# p128b.net
KiCad netlist of a schematic drawn in EAGLE
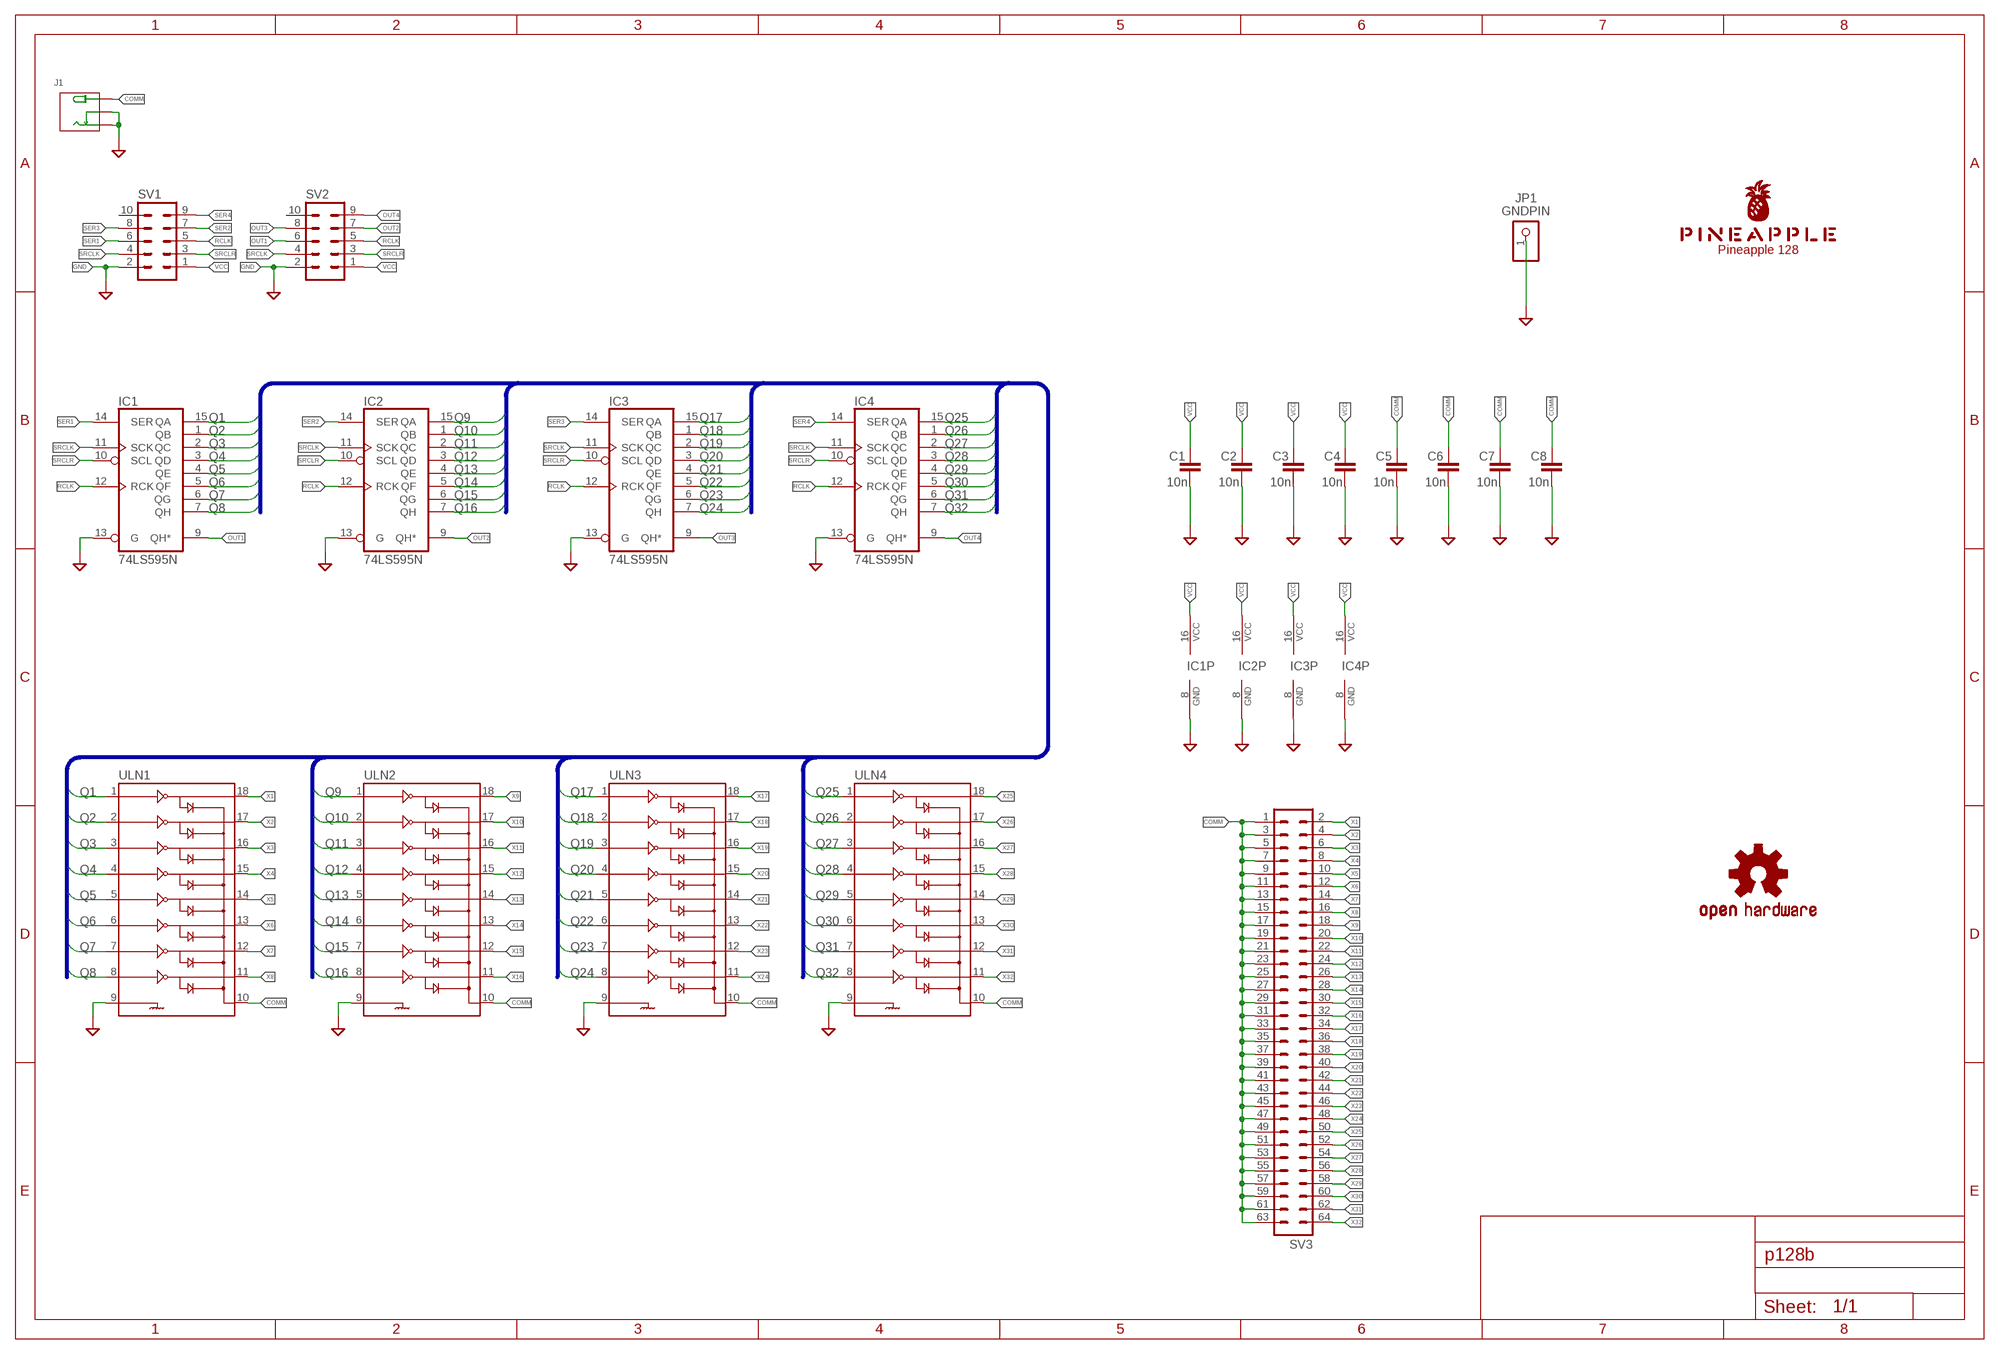
[diagram p0: schematic, sheet 1]

(export (version "E")
  (design (tool "Eeschema 10.0.6"))
  (components
    (comp (ref "C1")
      (value "10n")
      (footprint "eagle-import:C025-024X044")
      (libsource (lib "eagle-import") (part "resistor_348_C-EU025-024X044"))
    )
    (comp (ref "C2")
      (value "10n")
      (footprint "eagle-import:C025-024X044")
      (libsource (lib "eagle-import") (part "resistor_348_C-EU025-024X044"))
    )
    (comp (ref "C3")
      (value "10n")
      (footprint "eagle-import:C025-024X044")
      (libsource (lib "eagle-import") (part "resistor_348_C-EU025-024X044"))
    )
    (comp (ref "C4")
      (value "10n")
      (footprint "eagle-import:C025-024X044")
      (libsource (lib "eagle-import") (part "resistor_348_C-EU025-024X044"))
    )
    (comp (ref "C5")
      (value "10n")
      (footprint "eagle-import:C025-024X044")
      (libsource (lib "eagle-import") (part "C-EU025-024X044"))
    )
    (comp (ref "C6")
      (value "10n")
      (footprint "eagle-import:C025-024X044")
      (libsource (lib "eagle-import") (part "resistor_348_C-EU025-024X044"))
    )
    (comp (ref "C7")
      (value "10n")
      (footprint "eagle-import:C025-024X044")
      (libsource (lib "eagle-import") (part "resistor_348_C-EU025-024X044"))
    )
    (comp (ref "C8")
      (value "10n")
      (footprint "eagle-import:C025-024X044")
      (libsource (lib "eagle-import") (part "resistor_348_C-EU025-024X044"))
    )
    (comp (ref "IC1")
      (value "74LS595N")
      (footprint "eagle-import:DIL16")
      (libsource (lib "eagle-import") (part "74595NLS"))
    )
    (comp (ref "IC2")
      (value "74LS595N")
      (footprint "eagle-import:DIL16")
      (libsource (lib "eagle-import") (part "74595NLS"))
    )
    (comp (ref "IC3")
      (value "74LS595N")
      (footprint "eagle-import:DIL16")
      (libsource (lib "eagle-import") (part "74595NLS"))
    )
    (comp (ref "IC4")
      (value "74LS595N")
      (footprint "eagle-import:DIL16")
      (libsource (lib "eagle-import") (part "74595NLS"))
    )
    (comp (ref "J1")
      (value "JACK-DC-005'DC-005'")
      (footprint "eagle-import:3P-L14.2_W11.0_H9.0MM")
      (libsource (lib "eagle-import") (part "JACK-DC-005'DC-005'"))
    )
    (comp (ref "JP1")
      (value "GNDPIN")
      (footprint "eagle-import:1X01")
      (libsource (lib "eagle-import") (part "PINHD-1X1"))
    )
    (comp (ref "LOGO1")
      (value "OSHW-LOGOS-COPPER")
      (footprint "eagle-import:OSHW-LOGO-S_COPPER")
      (libsource (lib "eagle-import") (part "OSHW-LOGOS-COPPER"))
    )
    (comp (ref "SV1")
      (value "ML10L")
      (footprint "eagle-import:ML10L")
      (libsource (lib "eagle-import") (part "ML10L"))
    )
    (comp (ref "SV2")
      (value "ML10L")
      (footprint "eagle-import:ML10L")
      (libsource (lib "eagle-import") (part "ML10L"))
    )
    (comp (ref "SV3")
      (value "ML64L")
      (footprint "eagle-import:ML64L")
      (libsource (lib "eagle-import") (part "ML64L"))
    )
    (comp (ref "U$1")
      (value "PINEAPPLE450_SILK")
      (footprint "eagle-import:PINEAPPLE450_SILK")
      (libsource (lib "eagle-import") (part "PINEAPPLE450_SILK"))
    )
    (comp (ref "ULN1")
      (value "ULN2803DIP")
      (footprint "eagle-import:DIL18")
      (libsource (lib "eagle-import") (part "ULN2803DIP"))
    )
    (comp (ref "ULN2")
      (value "ULN2803DIP")
      (footprint "eagle-import:DIL18")
      (libsource (lib "eagle-import") (part "ULN2803DIP"))
    )
    (comp (ref "ULN3")
      (value "ULN2803DIP")
      (footprint "eagle-import:DIL18")
      (libsource (lib "eagle-import") (part "ULN2803DIP"))
    )
    (comp (ref "ULN4")
      (value "ULN2803DIP")
      (footprint "eagle-import:DIL18")
      (libsource (lib "eagle-import") (part "ULN2803DIP"))
    )
  )
  (nets
    (net (code "1") (name "/Q1") (class "Default")
      (node (ref "IC1") (pin "15") (pinfunction "QA_15") (pintype "tri_state"))
      (node (ref "ULN1") (pin "1") (pinfunction "1_1") (pintype "bidirectional"))
    )
    (net (code "2") (name "/Q2") (class "Default")
      (node (ref "IC1") (pin "1") (pinfunction "QB_1") (pintype "tri_state"))
      (node (ref "ULN1") (pin "2") (pinfunction "2_2") (pintype "bidirectional"))
    )
    (net (code "3") (name "/Q3") (class "Default")
      (node (ref "IC1") (pin "2") (pinfunction "QC_2") (pintype "tri_state"))
      (node (ref "ULN1") (pin "3") (pinfunction "3_3") (pintype "bidirectional"))
    )
    (net (code "4") (name "/Q4") (class "Default")
      (node (ref "IC1") (pin "3") (pinfunction "QD_3") (pintype "tri_state"))
      (node (ref "ULN1") (pin "4") (pinfunction "4_4") (pintype "bidirectional"))
    )
    (net (code "5") (name "/Q5") (class "Default")
      (node (ref "IC1") (pin "4") (pinfunction "QE_4") (pintype "tri_state"))
      (node (ref "ULN1") (pin "5") (pinfunction "5_5") (pintype "bidirectional"))
    )
    (net (code "6") (name "/Q6") (class "Default")
      (node (ref "IC1") (pin "5") (pinfunction "QF_5") (pintype "tri_state"))
      (node (ref "ULN1") (pin "6") (pinfunction "6_6") (pintype "bidirectional"))
    )
    (net (code "7") (name "/Q7") (class "Default")
      (node (ref "IC1") (pin "6") (pinfunction "QG_6") (pintype "tri_state"))
      (node (ref "ULN1") (pin "7") (pinfunction "7_7") (pintype "bidirectional"))
    )
    (net (code "8") (name "/Q8") (class "Default")
      (node (ref "IC1") (pin "7") (pinfunction "QH_7") (pintype "tri_state"))
      (node (ref "ULN1") (pin "8") (pinfunction "8_8") (pintype "bidirectional"))
    )
    (net (code "9") (name "/Q9") (class "Default")
      (node (ref "IC2") (pin "15") (pinfunction "QA_15") (pintype "tri_state"))
      (node (ref "ULN2") (pin "1") (pinfunction "1_1") (pintype "bidirectional"))
    )
    (net (code "10") (name "/Q10") (class "Default")
      (node (ref "IC2") (pin "1") (pinfunction "QB_1") (pintype "tri_state"))
      (node (ref "ULN2") (pin "2") (pinfunction "2_2") (pintype "bidirectional"))
    )
    (net (code "11") (name "/Q11") (class "Default")
      (node (ref "IC2") (pin "2") (pinfunction "QC_2") (pintype "tri_state"))
      (node (ref "ULN2") (pin "3") (pinfunction "3_3") (pintype "bidirectional"))
    )
    (net (code "12") (name "/Q12") (class "Default")
      (node (ref "IC2") (pin "3") (pinfunction "QD_3") (pintype "tri_state"))
      (node (ref "ULN2") (pin "4") (pinfunction "4_4") (pintype "bidirectional"))
    )
    (net (code "13") (name "/Q13") (class "Default")
      (node (ref "IC2") (pin "4") (pinfunction "QE_4") (pintype "tri_state"))
      (node (ref "ULN2") (pin "5") (pinfunction "5_5") (pintype "bidirectional"))
    )
    (net (code "14") (name "/Q14") (class "Default")
      (node (ref "IC2") (pin "5") (pinfunction "QF_5") (pintype "tri_state"))
      (node (ref "ULN2") (pin "6") (pinfunction "6_6") (pintype "bidirectional"))
    )
    (net (code "15") (name "/Q15") (class "Default")
      (node (ref "IC2") (pin "6") (pinfunction "QG_6") (pintype "tri_state"))
      (node (ref "ULN2") (pin "7") (pinfunction "7_7") (pintype "bidirectional"))
    )
    (net (code "16") (name "/Q16") (class "Default")
      (node (ref "IC2") (pin "7") (pinfunction "QH_7") (pintype "tri_state"))
      (node (ref "ULN2") (pin "8") (pinfunction "8_8") (pintype "bidirectional"))
    )
    (net (code "17") (name "/Q17") (class "Default")
      (node (ref "IC3") (pin "15") (pinfunction "QA_15") (pintype "tri_state"))
      (node (ref "ULN3") (pin "1") (pinfunction "1_1") (pintype "bidirectional"))
    )
    (net (code "18") (name "/Q18") (class "Default")
      (node (ref "IC3") (pin "1") (pinfunction "QB_1") (pintype "tri_state"))
      (node (ref "ULN3") (pin "2") (pinfunction "2_2") (pintype "bidirectional"))
    )
    (net (code "19") (name "/Q19") (class "Default")
      (node (ref "IC3") (pin "2") (pinfunction "QC_2") (pintype "tri_state"))
      (node (ref "ULN3") (pin "3") (pinfunction "3_3") (pintype "bidirectional"))
    )
    (net (code "20") (name "/Q20") (class "Default")
      (node (ref "IC3") (pin "3") (pinfunction "QD_3") (pintype "tri_state"))
      (node (ref "ULN3") (pin "4") (pinfunction "4_4") (pintype "bidirectional"))
    )
    (net (code "21") (name "/Q21") (class "Default")
      (node (ref "IC3") (pin "4") (pinfunction "QE_4") (pintype "tri_state"))
      (node (ref "ULN3") (pin "5") (pinfunction "5_5") (pintype "bidirectional"))
    )
    (net (code "22") (name "/Q22") (class "Default")
      (node (ref "IC3") (pin "5") (pinfunction "QF_5") (pintype "tri_state"))
      (node (ref "ULN3") (pin "6") (pinfunction "6_6") (pintype "bidirectional"))
    )
    (net (code "23") (name "/Q23") (class "Default")
      (node (ref "IC3") (pin "6") (pinfunction "QG_6") (pintype "tri_state"))
      (node (ref "ULN3") (pin "7") (pinfunction "7_7") (pintype "bidirectional"))
    )
    (net (code "24") (name "/Q24") (class "Default")
      (node (ref "IC3") (pin "7") (pinfunction "QH_7") (pintype "tri_state"))
      (node (ref "ULN3") (pin "8") (pinfunction "8_8") (pintype "bidirectional"))
    )
    (net (code "25") (name "/Q25") (class "Default")
      (node (ref "IC4") (pin "15") (pinfunction "QA_15") (pintype "tri_state"))
      (node (ref "ULN4") (pin "1") (pinfunction "1_1") (pintype "bidirectional"))
    )
    (net (code "26") (name "/Q26") (class "Default")
      (node (ref "IC4") (pin "1") (pinfunction "QB_1") (pintype "tri_state"))
      (node (ref "ULN4") (pin "2") (pinfunction "2_2") (pintype "bidirectional"))
    )
    (net (code "27") (name "/Q27") (class "Default")
      (node (ref "IC4") (pin "2") (pinfunction "QC_2") (pintype "tri_state"))
      (node (ref "ULN4") (pin "3") (pinfunction "3_3") (pintype "bidirectional"))
    )
    (net (code "28") (name "/Q28") (class "Default")
      (node (ref "IC4") (pin "3") (pinfunction "QD_3") (pintype "tri_state"))
      (node (ref "ULN4") (pin "4") (pinfunction "4_4") (pintype "bidirectional"))
    )
    (net (code "29") (name "/Q29") (class "Default")
      (node (ref "IC4") (pin "4") (pinfunction "QE_4") (pintype "tri_state"))
      (node (ref "ULN4") (pin "5") (pinfunction "5_5") (pintype "bidirectional"))
    )
    (net (code "30") (name "/Q30") (class "Default")
      (node (ref "IC4") (pin "5") (pinfunction "QF_5") (pintype "tri_state"))
      (node (ref "ULN4") (pin "6") (pinfunction "6_6") (pintype "bidirectional"))
    )
    (net (code "31") (name "/Q31") (class "Default")
      (node (ref "IC4") (pin "6") (pinfunction "QG_6") (pintype "tri_state"))
      (node (ref "ULN4") (pin "7") (pinfunction "7_7") (pintype "bidirectional"))
    )
    (net (code "32") (name "/Q32") (class "Default")
      (node (ref "IC4") (pin "7") (pinfunction "QH_7") (pintype "tri_state"))
      (node (ref "ULN4") (pin "8") (pinfunction "8_8") (pintype "bidirectional"))
    )
    (net (code "33") (name "COMM") (class "Default")
      (node (ref "C5") (pin "1") (pinfunction "1_1") (pintype "passive"))
      (node (ref "C6") (pin "1") (pinfunction "1_1") (pintype "passive"))
      (node (ref "C7") (pin "1") (pinfunction "1_1") (pintype "passive"))
      (node (ref "C8") (pin "1") (pinfunction "1_1") (pintype "passive"))
      (node (ref "J1") (pin "+") (pinfunction "+_+") (pintype "bidirectional"))
      (node (ref "SV3") (pin "1") (pinfunction "1_1") (pintype "passive"))
      (node (ref "SV3") (pin "11") (pinfunction "11_11") (pintype "passive"))
      (node (ref "SV3") (pin "13") (pinfunction "13_13") (pintype "passive"))
      (node (ref "SV3") (pin "15") (pinfunction "15_15") (pintype "passive"))
      (node (ref "SV3") (pin "17") (pinfunction "17_17") (pintype "passive"))
      (node (ref "SV3") (pin "19") (pinfunction "19_19") (pintype "passive"))
      (node (ref "SV3") (pin "21") (pinfunction "21_21") (pintype "passive"))
      (node (ref "SV3") (pin "23") (pinfunction "23_23") (pintype "passive"))
      (node (ref "SV3") (pin "25") (pinfunction "25_25") (pintype "passive"))
      (node (ref "SV3") (pin "27") (pinfunction "27_27") (pintype "passive"))
      (node (ref "SV3") (pin "29") (pinfunction "29_29") (pintype "passive"))
      (node (ref "SV3") (pin "3") (pinfunction "3_3") (pintype "passive"))
      (node (ref "SV3") (pin "31") (pinfunction "31_31") (pintype "passive"))
      (node (ref "SV3") (pin "33") (pinfunction "33_33") (pintype "passive"))
      (node (ref "SV3") (pin "35") (pinfunction "35_35") (pintype "passive"))
      (node (ref "SV3") (pin "37") (pinfunction "37_37") (pintype "passive"))
      (node (ref "SV3") (pin "39") (pinfunction "39_39") (pintype "passive"))
      (node (ref "SV3") (pin "41") (pinfunction "41_41") (pintype "passive"))
      (node (ref "SV3") (pin "43") (pinfunction "43_43") (pintype "passive"))
      (node (ref "SV3") (pin "45") (pinfunction "45_45") (pintype "passive"))
      (node (ref "SV3") (pin "47") (pinfunction "47_47") (pintype "passive"))
      (node (ref "SV3") (pin "49") (pinfunction "49_49") (pintype "passive"))
      (node (ref "SV3") (pin "5") (pinfunction "5_5") (pintype "passive"))
      (node (ref "SV3") (pin "51") (pinfunction "51_51") (pintype "passive"))
      (node (ref "SV3") (pin "53") (pinfunction "53_53") (pintype "passive"))
      (node (ref "SV3") (pin "55") (pinfunction "55_55") (pintype "passive"))
      (node (ref "SV3") (pin "57") (pinfunction "57_57") (pintype "passive"))
      (node (ref "SV3") (pin "59") (pinfunction "59_59") (pintype "passive"))
      (node (ref "SV3") (pin "61") (pinfunction "61_61") (pintype "passive"))
      (node (ref "SV3") (pin "63") (pinfunction "63_63") (pintype "passive"))
      (node (ref "SV3") (pin "7") (pinfunction "7_7") (pintype "passive"))
      (node (ref "SV3") (pin "9") (pinfunction "9_9") (pintype "passive"))
      (node (ref "ULN1") (pin "10") (pinfunction "10_10") (pintype "bidirectional"))
      (node (ref "ULN2") (pin "10") (pinfunction "10_10") (pintype "bidirectional"))
      (node (ref "ULN3") (pin "10") (pinfunction "10_10") (pintype "bidirectional"))
      (node (ref "ULN4") (pin "10") (pinfunction "10_10") (pintype "bidirectional"))
    )
    (net (code "34") (name "GND") (class "Default")
      (node (ref "C1") (pin "2") (pinfunction "2_2") (pintype "passive"))
      (node (ref "C2") (pin "2") (pinfunction "2_2") (pintype "passive"))
      (node (ref "C3") (pin "2") (pinfunction "2_2") (pintype "passive"))
      (node (ref "C4") (pin "2") (pinfunction "2_2") (pintype "passive"))
      (node (ref "C5") (pin "2") (pinfunction "2_2") (pintype "passive"))
      (node (ref "C6") (pin "2") (pinfunction "2_2") (pintype "passive"))
      (node (ref "C7") (pin "2") (pinfunction "2_2") (pintype "passive"))
      (node (ref "C8") (pin "2") (pinfunction "2_2") (pintype "passive"))
      (node (ref "IC1") (pin "13") (pinfunction "G_13") (pintype "input"))
      (node (ref "IC1") (pin "8") (pinfunction "GND_8") (pintype "power_in"))
      (node (ref "IC2") (pin "13") (pinfunction "G_13") (pintype "input"))
      (node (ref "IC2") (pin "8") (pinfunction "GND_8") (pintype "power_in"))
      (node (ref "IC3") (pin "13") (pinfunction "G_13") (pintype "input"))
      (node (ref "IC3") (pin "8") (pinfunction "GND_8") (pintype "power_in"))
      (node (ref "IC4") (pin "13") (pinfunction "G_13") (pintype "input"))
      (node (ref "IC4") (pin "8") (pinfunction "GND_8") (pintype "power_in"))
      (node (ref "J1") (pin "-1") (pinfunction "-_-1") (pintype "bidirectional"))
      (node (ref "J1") (pin "-2") (pinfunction "CDN_-2") (pintype "bidirectional"))
      (node (ref "JP1") (pin "1") (pinfunction "1_1") (pintype "passive"))
      (node (ref "SV1") (pin "2") (pinfunction "2_2") (pintype "passive"))
      (node (ref "SV2") (pin "2") (pinfunction "2_2") (pintype "passive"))
      (node (ref "ULN1") (pin "9") (pinfunction "9_9") (pintype "bidirectional"))
      (node (ref "ULN2") (pin "9") (pinfunction "9_9") (pintype "bidirectional"))
      (node (ref "ULN3") (pin "9") (pinfunction "9_9") (pintype "bidirectional"))
      (node (ref "ULN4") (pin "9") (pinfunction "9_9") (pintype "bidirectional"))
    )
    (net (code "35") (name "OUT1") (class "Default")
      (node (ref "IC1") (pin "9") (pinfunction "QH*_9") (pintype "tri_state"))
      (node (ref "SV2") (pin "6") (pinfunction "6_6") (pintype "passive"))
    )
    (net (code "36") (name "OUT2") (class "Default")
      (node (ref "IC2") (pin "9") (pinfunction "QH*_9") (pintype "tri_state"))
      (node (ref "SV2") (pin "7") (pinfunction "7_7") (pintype "passive"))
    )
    (net (code "37") (name "OUT3") (class "Default")
      (node (ref "IC3") (pin "9") (pinfunction "QH*_9") (pintype "tri_state"))
      (node (ref "SV2") (pin "8") (pinfunction "8_8") (pintype "passive"))
    )
    (net (code "38") (name "OUT4") (class "Default")
      (node (ref "IC4") (pin "9") (pinfunction "QH*_9") (pintype "tri_state"))
      (node (ref "SV2") (pin "9") (pinfunction "9_9") (pintype "passive"))
    )
    (net (code "39") (name "RCLK") (class "Default")
      (node (ref "IC1") (pin "12") (pinfunction "RCK_12") (pintype "input"))
      (node (ref "IC2") (pin "12") (pinfunction "RCK_12") (pintype "input"))
      (node (ref "IC3") (pin "12") (pinfunction "RCK_12") (pintype "input"))
      (node (ref "IC4") (pin "12") (pinfunction "RCK_12") (pintype "input"))
      (node (ref "SV1") (pin "5") (pinfunction "5_5") (pintype "passive"))
      (node (ref "SV2") (pin "5") (pinfunction "5_5") (pintype "passive"))
    )
    (net (code "40") (name "SER1") (class "Default")
      (node (ref "IC1") (pin "14") (pinfunction "SER_14") (pintype "input"))
      (node (ref "SV1") (pin "6") (pinfunction "6_6") (pintype "passive"))
    )
    (net (code "41") (name "SER2") (class "Default")
      (node (ref "IC2") (pin "14") (pinfunction "SER_14") (pintype "input"))
      (node (ref "SV1") (pin "7") (pinfunction "7_7") (pintype "passive"))
    )
    (net (code "42") (name "SER3") (class "Default")
      (node (ref "IC3") (pin "14") (pinfunction "SER_14") (pintype "input"))
      (node (ref "SV1") (pin "8") (pinfunction "8_8") (pintype "passive"))
    )
    (net (code "43") (name "SER4") (class "Default")
      (node (ref "IC4") (pin "14") (pinfunction "SER_14") (pintype "input"))
      (node (ref "SV1") (pin "9") (pinfunction "9_9") (pintype "passive"))
    )
    (net (code "44") (name "SRCLK") (class "Default")
      (node (ref "IC1") (pin "11") (pinfunction "SCK_11") (pintype "input"))
      (node (ref "IC2") (pin "11") (pinfunction "SCK_11") (pintype "input"))
      (node (ref "IC3") (pin "11") (pinfunction "SCK_11") (pintype "input"))
      (node (ref "IC4") (pin "11") (pinfunction "SCK_11") (pintype "input"))
      (node (ref "SV1") (pin "4") (pinfunction "4_4") (pintype "passive"))
      (node (ref "SV2") (pin "4") (pinfunction "4_4") (pintype "passive"))
    )
    (net (code "45") (name "SRCLR") (class "Default")
      (node (ref "IC1") (pin "10") (pinfunction "SCL_10") (pintype "input"))
      (node (ref "IC2") (pin "10") (pinfunction "SCL_10") (pintype "input"))
      (node (ref "IC3") (pin "10") (pinfunction "SCL_10") (pintype "input"))
      (node (ref "IC4") (pin "10") (pinfunction "SCL_10") (pintype "input"))
      (node (ref "SV1") (pin "3") (pinfunction "3_3") (pintype "passive"))
      (node (ref "SV2") (pin "3") (pinfunction "3_3") (pintype "passive"))
    )
    (net (code "46") (name "VCC") (class "Default")
      (node (ref "C1") (pin "1") (pinfunction "1_1") (pintype "passive"))
      (node (ref "C2") (pin "1") (pinfunction "1_1") (pintype "passive"))
      (node (ref "C3") (pin "1") (pinfunction "1_1") (pintype "passive"))
      (node (ref "C4") (pin "1") (pinfunction "1_1") (pintype "passive"))
      (node (ref "IC1") (pin "16") (pinfunction "VCC_16") (pintype "power_in"))
      (node (ref "IC2") (pin "16") (pinfunction "VCC_16") (pintype "power_in"))
      (node (ref "IC3") (pin "16") (pinfunction "VCC_16") (pintype "power_in"))
      (node (ref "IC4") (pin "16") (pinfunction "VCC_16") (pintype "power_in"))
      (node (ref "SV1") (pin "1") (pinfunction "1_1") (pintype "passive"))
      (node (ref "SV2") (pin "1") (pinfunction "1_1") (pintype "passive"))
    )
    (net (code "47") (name "X1") (class "Default")
      (node (ref "SV3") (pin "2") (pinfunction "2_2") (pintype "passive"))
      (node (ref "ULN1") (pin "18") (pinfunction "18_18") (pintype "bidirectional"))
    )
    (net (code "48") (name "X2") (class "Default")
      (node (ref "SV3") (pin "4") (pinfunction "4_4") (pintype "passive"))
      (node (ref "ULN1") (pin "17") (pinfunction "17_17") (pintype "bidirectional"))
    )
    (net (code "49") (name "X3") (class "Default")
      (node (ref "SV3") (pin "6") (pinfunction "6_6") (pintype "passive"))
      (node (ref "ULN1") (pin "16") (pinfunction "16_16") (pintype "bidirectional"))
    )
    (net (code "50") (name "X4") (class "Default")
      (node (ref "SV3") (pin "8") (pinfunction "8_8") (pintype "passive"))
      (node (ref "ULN1") (pin "15") (pinfunction "15_15") (pintype "bidirectional"))
    )
    (net (code "51") (name "X5") (class "Default")
      (node (ref "SV3") (pin "10") (pinfunction "10_10") (pintype "passive"))
      (node (ref "ULN1") (pin "14") (pinfunction "14_14") (pintype "bidirectional"))
    )
    (net (code "52") (name "X6") (class "Default")
      (node (ref "SV3") (pin "12") (pinfunction "12_12") (pintype "passive"))
      (node (ref "ULN1") (pin "13") (pinfunction "13_13") (pintype "bidirectional"))
    )
    (net (code "53") (name "X7") (class "Default")
      (node (ref "SV3") (pin "14") (pinfunction "14_14") (pintype "passive"))
      (node (ref "ULN1") (pin "12") (pinfunction "12_12") (pintype "bidirectional"))
    )
    (net (code "54") (name "X8") (class "Default")
      (node (ref "SV3") (pin "16") (pinfunction "16_16") (pintype "passive"))
      (node (ref "ULN1") (pin "11") (pinfunction "11_11") (pintype "bidirectional"))
    )
    (net (code "55") (name "X9") (class "Default")
      (node (ref "SV3") (pin "18") (pinfunction "18_18") (pintype "passive"))
      (node (ref "ULN2") (pin "18") (pinfunction "18_18") (pintype "bidirectional"))
    )
    (net (code "56") (name "X10") (class "Default")
      (node (ref "SV3") (pin "20") (pinfunction "20_20") (pintype "passive"))
      (node (ref "ULN2") (pin "17") (pinfunction "17_17") (pintype "bidirectional"))
    )
    (net (code "57") (name "X11") (class "Default")
      (node (ref "SV3") (pin "22") (pinfunction "22_22") (pintype "passive"))
      (node (ref "ULN2") (pin "16") (pinfunction "16_16") (pintype "bidirectional"))
    )
    (net (code "58") (name "X12") (class "Default")
      (node (ref "SV3") (pin "24") (pinfunction "24_24") (pintype "passive"))
      (node (ref "ULN2") (pin "15") (pinfunction "15_15") (pintype "bidirectional"))
    )
    (net (code "59") (name "X13") (class "Default")
      (node (ref "SV3") (pin "26") (pinfunction "26_26") (pintype "passive"))
      (node (ref "ULN2") (pin "14") (pinfunction "14_14") (pintype "bidirectional"))
    )
    (net (code "60") (name "X14") (class "Default")
      (node (ref "SV3") (pin "28") (pinfunction "28_28") (pintype "passive"))
      (node (ref "ULN2") (pin "13") (pinfunction "13_13") (pintype "bidirectional"))
    )
    (net (code "61") (name "X15") (class "Default")
      (node (ref "SV3") (pin "30") (pinfunction "30_30") (pintype "passive"))
      (node (ref "ULN2") (pin "12") (pinfunction "12_12") (pintype "bidirectional"))
    )
    (net (code "62") (name "X16") (class "Default")
      (node (ref "SV3") (pin "32") (pinfunction "32_32") (pintype "passive"))
      (node (ref "ULN2") (pin "11") (pinfunction "11_11") (pintype "bidirectional"))
    )
    (net (code "63") (name "X17") (class "Default")
      (node (ref "SV3") (pin "34") (pinfunction "34_34") (pintype "passive"))
      (node (ref "ULN3") (pin "18") (pinfunction "18_18") (pintype "bidirectional"))
    )
    (net (code "64") (name "X18") (class "Default")
      (node (ref "SV3") (pin "36") (pinfunction "36_36") (pintype "passive"))
      (node (ref "ULN3") (pin "17") (pinfunction "17_17") (pintype "bidirectional"))
    )
    (net (code "65") (name "X19") (class "Default")
      (node (ref "SV3") (pin "38") (pinfunction "38_38") (pintype "passive"))
      (node (ref "ULN3") (pin "16") (pinfunction "16_16") (pintype "bidirectional"))
    )
    (net (code "66") (name "X20") (class "Default")
      (node (ref "SV3") (pin "40") (pinfunction "40_40") (pintype "passive"))
      (node (ref "ULN3") (pin "15") (pinfunction "15_15") (pintype "bidirectional"))
    )
    (net (code "67") (name "X21") (class "Default")
      (node (ref "SV3") (pin "42") (pinfunction "42_42") (pintype "passive"))
      (node (ref "ULN3") (pin "14") (pinfunction "14_14") (pintype "bidirectional"))
    )
    (net (code "68") (name "X22") (class "Default")
      (node (ref "SV3") (pin "44") (pinfunction "44_44") (pintype "passive"))
      (node (ref "ULN3") (pin "13") (pinfunction "13_13") (pintype "bidirectional"))
    )
    (net (code "69") (name "X23") (class "Default")
      (node (ref "SV3") (pin "46") (pinfunction "46_46") (pintype "passive"))
      (node (ref "ULN3") (pin "12") (pinfunction "12_12") (pintype "bidirectional"))
    )
    (net (code "70") (name "X24") (class "Default")
      (node (ref "SV3") (pin "48") (pinfunction "48_48") (pintype "passive"))
      (node (ref "ULN3") (pin "11") (pinfunction "11_11") (pintype "bidirectional"))
    )
    (net (code "71") (name "X25") (class "Default")
      (node (ref "SV3") (pin "50") (pinfunction "50_50") (pintype "passive"))
      (node (ref "ULN4") (pin "18") (pinfunction "18_18") (pintype "bidirectional"))
    )
    (net (code "72") (name "X26") (class "Default")
      (node (ref "SV3") (pin "52") (pinfunction "52_52") (pintype "passive"))
      (node (ref "ULN4") (pin "17") (pinfunction "17_17") (pintype "bidirectional"))
    )
    (net (code "73") (name "X27") (class "Default")
      (node (ref "SV3") (pin "54") (pinfunction "54_54") (pintype "passive"))
      (node (ref "ULN4") (pin "16") (pinfunction "16_16") (pintype "bidirectional"))
    )
    (net (code "74") (name "X28") (class "Default")
      (node (ref "SV3") (pin "56") (pinfunction "56_56") (pintype "passive"))
      (node (ref "ULN4") (pin "15") (pinfunction "15_15") (pintype "bidirectional"))
    )
    (net (code "75") (name "X29") (class "Default")
      (node (ref "SV3") (pin "58") (pinfunction "58_58") (pintype "passive"))
      (node (ref "ULN4") (pin "14") (pinfunction "14_14") (pintype "bidirectional"))
    )
    (net (code "76") (name "X30") (class "Default")
      (node (ref "SV3") (pin "60") (pinfunction "60_60") (pintype "passive"))
      (node (ref "ULN4") (pin "13") (pinfunction "13_13") (pintype "bidirectional"))
    )
    (net (code "77") (name "X31") (class "Default")
      (node (ref "SV3") (pin "62") (pinfunction "62_62") (pintype "passive"))
      (node (ref "ULN4") (pin "12") (pinfunction "12_12") (pintype "bidirectional"))
    )
    (net (code "78") (name "X32") (class "Default")
      (node (ref "SV3") (pin "64") (pinfunction "64_64") (pintype "passive"))
      (node (ref "ULN4") (pin "11") (pinfunction "11_11") (pintype "bidirectional"))
    )
    (net (code "79") (name "unconnected-(SV1-Pad10)") (class "Default")
      (node (ref "SV1") (pin "10") (pinfunction "10_10") (pintype "passive"))
    )
    (net (code "80") (name "unconnected-(SV2-Pad10)") (class "Default")
      (node (ref "SV2") (pin "10") (pinfunction "10_10") (pintype "passive"))
    )
  )
)
